# Sheet1_2.net
KiCad netlist of a schematic drawn in Altium Designer
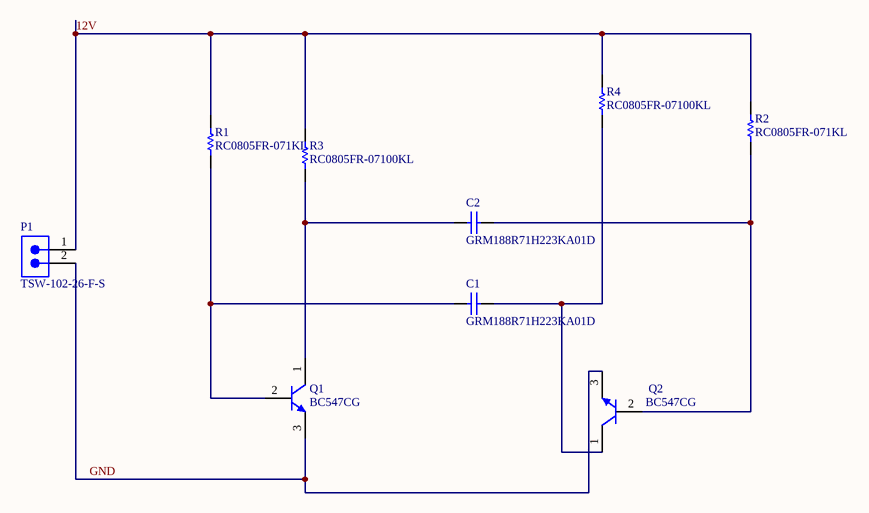
[diagram p0: Sheet1(2).SchDoc]

(export (version "E")
  (design (tool "Eeschema 10.0.6"))
  (components
    (comp (ref "C1")
      (value "GRM188R71H223KA01D")
      (footprint "CAPC1608X90X35ML10T15")
      (fields (field (name "MANUFACTURER") "Murata"))
      (libsource (lib "Altium Content Vault") (part "CAP"))
    )
    (comp (ref "C2")
      (value "GRM188R71H223KA01D")
      (footprint "CAPC1608X90X35ML10T15")
      (fields (field (name "MANUFACTURER") "Murata"))
      (libsource (lib "Altium Content Vault") (part "CAP"))
    )
    (comp (ref "P1")
      (value "TSW-102-26-F-S")
      (footprint "SMTC-TSW-102-26-XX-S")
      (description "0.025\" SQ Post Header, Through-hole, Vertical, -55 to 125 degC, 2.54 mm Pitch, 2-Pin, Male, RoHS")
      (fields (field (name "MANUFACTURER") "Samtec"))
      (libsource (lib "Altium Content Vault") (part "SMTC-TSW-102-X-X-S-X"))
    )
    (comp (ref "Q1")
      (value "BC547CG")
      (footprint "ONSC-TO-92-3-29-11")
      (description "Amplifier Transistor, NPN Silicon, 3-Pin TO-92, Pb-Free, Bulk Box")
      (fields (field (name "MANUFACTURER") "On Semiconductor"))
      (libsource (lib "Altium Content Vault") (part "ONSC-NPN-C1B2E3-3"))
    )
    (comp (ref "Q2")
      (value "BC547CG")
      (footprint "ONSC-TO-92-3-29-11")
      (description "Amplifier Transistor, NPN Silicon, 3-Pin TO-92, Pb-Free, Bulk Box")
      (fields (field (name "MANUFACTURER") "On Semiconductor"))
      (libsource (lib "Altium Content Vault") (part "ONSC-NPN-C1B2E3-3"))
    )
    (comp (ref "R1")
      (value "RC0805FR-071KL")
      (footprint "RESC2013X60X35ML10T20")
      (description "Chip Resistor, 1 KOhm, +/- 1%, 125 mW, -55 to 155 degC, 0805 (2012 Metric), RoHS, Tape and Reel")
      (fields (field (name "TOLERANCE") "1%") (field (name "MANUFACTURER") "Yageo"))
      (libsource (lib "Altium Content Vault") (part "RES-2"))
    )
    (comp (ref "R2")
      (value "RC0805FR-071KL")
      (footprint "RESC2013X60X35ML10T20")
      (description "Chip Resistor, 1 KOhm, +/- 1%, 125 mW, -55 to 155 degC, 0805 (2012 Metric), RoHS, Tape and Reel")
      (fields (field (name "TOLERANCE") "1%") (field (name "MANUFACTURER") "Yageo"))
      (libsource (lib "Altium Content Vault") (part "RES-2"))
    )
    (comp (ref "R3")
      (value "RC0805FR-07100KL")
      (footprint "RESC2013X60X35ML10T20")
      (description "Chip Resistor, 100 KOhm, +/- 1%, 0.125 W, -55 to 155 degC, 0805 (2012 Metric), RoHS, Tape and Reel")
      (fields (field (name "MANUFACTURER") "Yageo") (field (name "TOLERANCE") "1%"))
      (libsource (lib "Altium Content Vault") (part "RES-2"))
    )
    (comp (ref "R4")
      (value "RC0805FR-07100KL")
      (footprint "RESC2013X60X35ML10T20")
      (description "Chip Resistor, 100 KOhm, +/- 1%, 0.125 W, -55 to 155 degC, 0805 (2012 Metric), RoHS, Tape and Reel")
      (fields (field (name "MANUFACTURER") "Yageo") (field (name "TOLERANCE") "1%"))
      (libsource (lib "Altium Content Vault") (part "RES-2"))
    )
  )
  (nets
    (net (code "1") (name "/12V") (class "Default")
      (node (ref "P1") (pin "1") (pinfunction "1_1") (pintype "passive"))
      (node (ref "R1") (pin "2") (pinfunction "2_2") (pintype "passive"))
      (node (ref "R2") (pin "2") (pinfunction "2_2") (pintype "passive"))
      (node (ref "R3") (pin "2") (pinfunction "2_2") (pintype "passive"))
      (node (ref "R4") (pin "2") (pinfunction "2_2") (pintype "passive"))
    )
    (net (code "2") (name "/GND") (class "Default")
      (node (ref "P1") (pin "2") (pinfunction "2_2") (pintype "passive"))
      (node (ref "Q1") (pin "3") (pinfunction "E_3") (pintype "passive"))
      (node (ref "Q2") (pin "3") (pinfunction "E_3") (pintype "passive"))
    )
    (net (code "3") (name "Net-(Q1-B)") (class "Default")
      (node (ref "C1") (pin "1") (pinfunction "1_1") (pintype "passive"))
      (node (ref "Q1") (pin "2") (pinfunction "B_2") (pintype "passive"))
      (node (ref "R1") (pin "1") (pinfunction "1_1") (pintype "passive"))
    )
    (net (code "4") (name "Net-(Q1-C)") (class "Default")
      (node (ref "C2") (pin "1") (pinfunction "1_1") (pintype "passive"))
      (node (ref "Q1") (pin "1") (pinfunction "C_1") (pintype "passive"))
      (node (ref "R3") (pin "1") (pinfunction "1_1") (pintype "passive"))
    )
    (net (code "5") (name "Net-(Q2-B)") (class "Default")
      (node (ref "C2") (pin "2") (pinfunction "2_2") (pintype "passive"))
      (node (ref "Q2") (pin "2") (pinfunction "B_2") (pintype "passive"))
      (node (ref "R2") (pin "1") (pinfunction "1_1") (pintype "passive"))
    )
    (net (code "6") (name "Net-(Q2-C)") (class "Default")
      (node (ref "C1") (pin "2") (pinfunction "2_2") (pintype "passive"))
      (node (ref "Q2") (pin "1") (pinfunction "C_1") (pintype "passive"))
      (node (ref "R4") (pin "1") (pinfunction "1_1") (pintype "passive"))
    )
  )
)
